# light_160mm_v1_0_less_vias.net
KiCad netlist of a schematic drawn in EAGLE
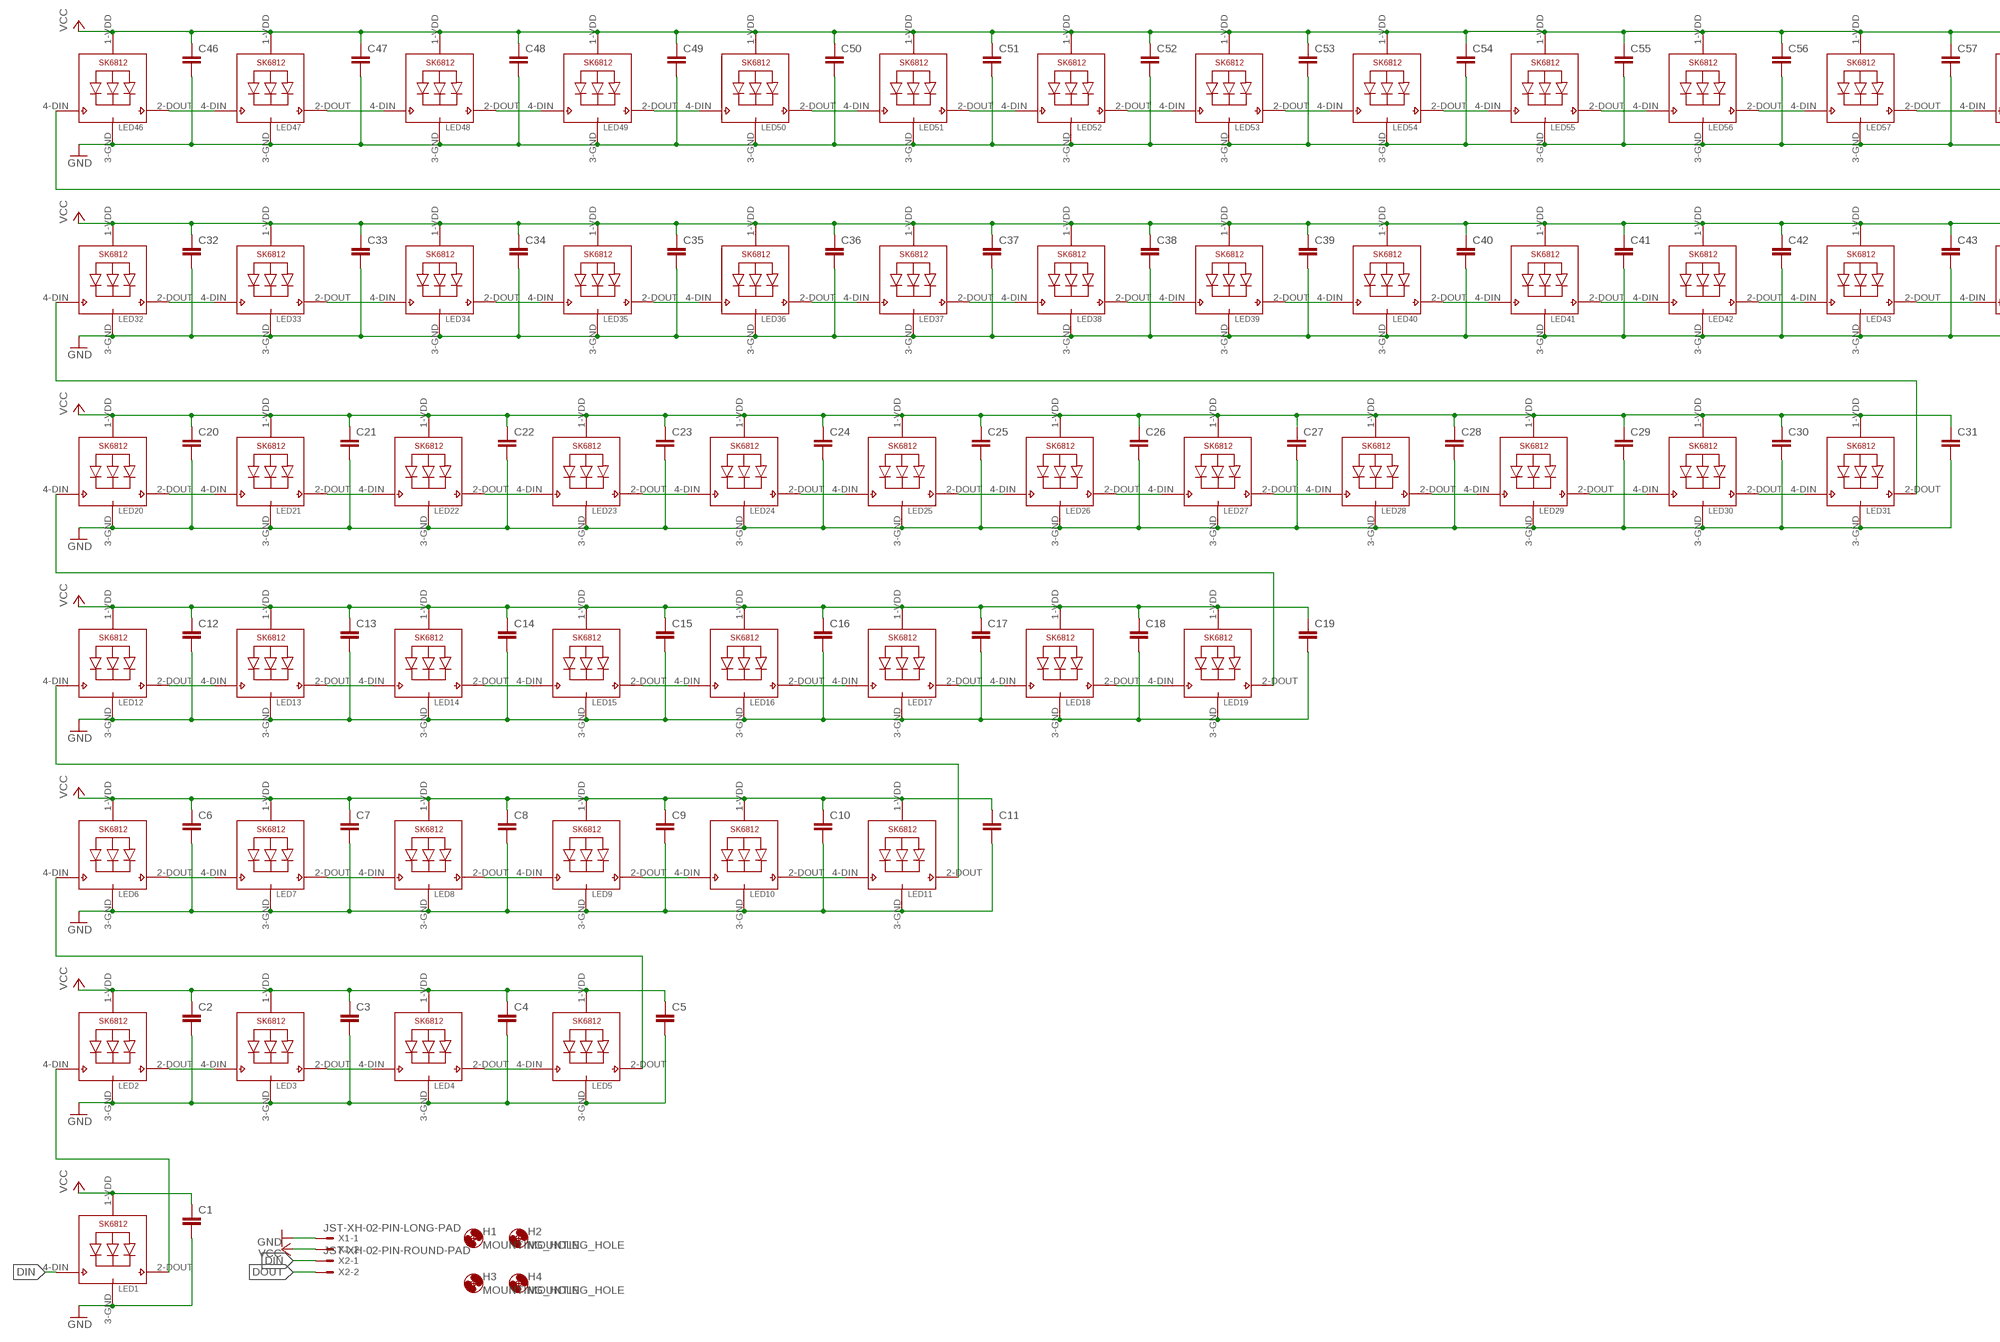
[diagram p0: schematic, sheet 1, part 1 of 2]
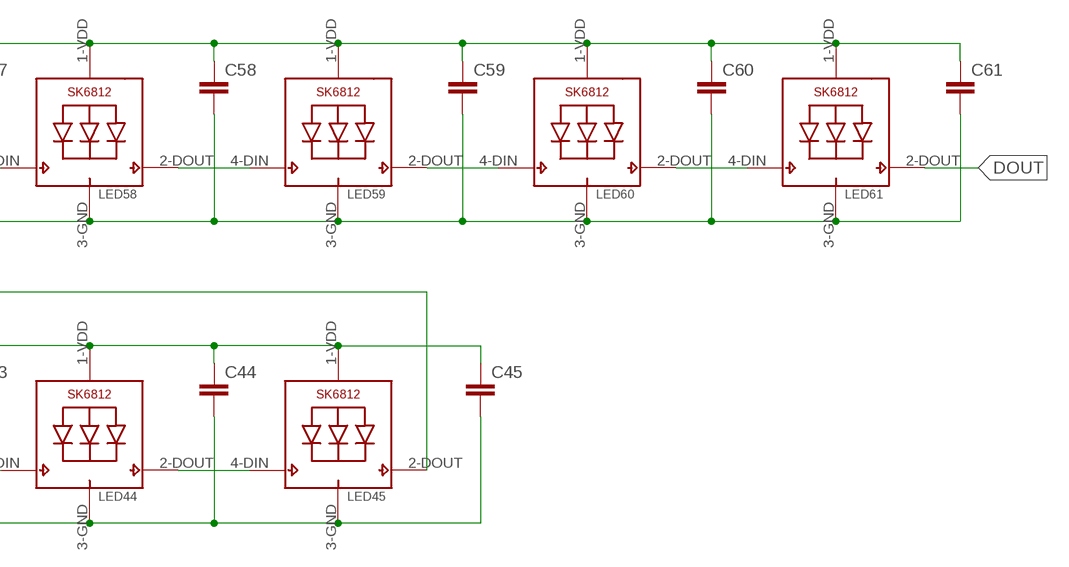
[diagram p1: schematic, sheet 1, part 2 of 2]

(export (version "E")
  (design (tool "Eeschema 10.0.6"))
  (components
    (comp (ref "C1")
      (value "C-EUC0805")
      (footprint "eagle-import:C0805")
      (libsource (lib "eagle-import") (part "C-EUC0805"))
    )
    (comp (ref "C2")
      (value "C-EUC0805")
      (footprint "eagle-import:C0805")
      (libsource (lib "eagle-import") (part "C-EUC0805"))
    )
    (comp (ref "C3")
      (value "C-EUC0805")
      (footprint "eagle-import:C0805")
      (libsource (lib "eagle-import") (part "C-EUC0805"))
    )
    (comp (ref "C4")
      (value "C-EUC0805")
      (footprint "eagle-import:C0805")
      (libsource (lib "eagle-import") (part "C-EUC0805"))
    )
    (comp (ref "C5")
      (value "C-EUC0805")
      (footprint "eagle-import:C0805")
      (libsource (lib "eagle-import") (part "C-EUC0805"))
    )
    (comp (ref "C6")
      (value "C-EUC0805")
      (footprint "eagle-import:C0805")
      (libsource (lib "eagle-import") (part "C-EUC0805"))
    )
    (comp (ref "C7")
      (value "C-EUC0805")
      (footprint "eagle-import:C0805")
      (libsource (lib "eagle-import") (part "C-EUC0805"))
    )
    (comp (ref "C8")
      (value "C-EUC0805")
      (footprint "eagle-import:C0805")
      (libsource (lib "eagle-import") (part "C-EUC0805"))
    )
    (comp (ref "C9")
      (value "C-EUC0805")
      (footprint "eagle-import:C0805")
      (libsource (lib "eagle-import") (part "C-EUC0805"))
    )
    (comp (ref "C10")
      (value "C-EUC0805")
      (footprint "eagle-import:C0805")
      (libsource (lib "eagle-import") (part "C-EUC0805"))
    )
    (comp (ref "C11")
      (value "C-EUC0805")
      (footprint "eagle-import:C0805")
      (libsource (lib "eagle-import") (part "C-EUC0805"))
    )
    (comp (ref "C12")
      (value "C-EUC0805")
      (footprint "eagle-import:C0805")
      (libsource (lib "eagle-import") (part "C-EUC0805"))
    )
    (comp (ref "C13")
      (value "C-EUC0805")
      (footprint "eagle-import:C0805")
      (libsource (lib "eagle-import") (part "C-EUC0805"))
    )
    (comp (ref "C14")
      (value "C-EUC0805")
      (footprint "eagle-import:C0805")
      (libsource (lib "eagle-import") (part "C-EUC0805"))
    )
    (comp (ref "C15")
      (value "C-EUC0805")
      (footprint "eagle-import:C0805")
      (libsource (lib "eagle-import") (part "C-EUC0805"))
    )
    (comp (ref "C16")
      (value "C-EUC0805")
      (footprint "eagle-import:C0805")
      (libsource (lib "eagle-import") (part "C-EUC0805"))
    )
    (comp (ref "C17")
      (value "C-EUC0805")
      (footprint "eagle-import:C0805")
      (libsource (lib "eagle-import") (part "C-EUC0805"))
    )
    (comp (ref "C18")
      (value "C-EUC0805")
      (footprint "eagle-import:C0805")
      (libsource (lib "eagle-import") (part "C-EUC0805"))
    )
    (comp (ref "C19")
      (value "C-EUC0805")
      (footprint "eagle-import:C0805")
      (libsource (lib "eagle-import") (part "C-EUC0805"))
    )
    (comp (ref "C20")
      (value "C-EUC0805")
      (footprint "eagle-import:C0805")
      (libsource (lib "eagle-import") (part "C-EUC0805"))
    )
    (comp (ref "C21")
      (value "C-EUC0805")
      (footprint "eagle-import:C0805")
      (libsource (lib "eagle-import") (part "C-EUC0805"))
    )
    (comp (ref "C22")
      (value "C-EUC0805")
      (footprint "eagle-import:C0805")
      (libsource (lib "eagle-import") (part "C-EUC0805"))
    )
    (comp (ref "C23")
      (value "C-EUC0805")
      (footprint "eagle-import:C0805")
      (libsource (lib "eagle-import") (part "C-EUC0805"))
    )
    (comp (ref "C24")
      (value "C-EUC0805")
      (footprint "eagle-import:C0805")
      (libsource (lib "eagle-import") (part "C-EUC0805"))
    )
    (comp (ref "C25")
      (value "C-EUC0805")
      (footprint "eagle-import:C0805")
      (libsource (lib "eagle-import") (part "C-EUC0805"))
    )
    (comp (ref "C26")
      (value "C-EUC0805")
      (footprint "eagle-import:C0805")
      (libsource (lib "eagle-import") (part "C-EUC0805"))
    )
    (comp (ref "C27")
      (value "C-EUC0805")
      (footprint "eagle-import:C0805")
      (libsource (lib "eagle-import") (part "C-EUC0805"))
    )
    (comp (ref "C28")
      (value "C-EUC0805")
      (footprint "eagle-import:C0805")
      (libsource (lib "eagle-import") (part "C-EUC0805"))
    )
    (comp (ref "C29")
      (value "C-EUC0805")
      (footprint "eagle-import:C0805")
      (libsource (lib "eagle-import") (part "C-EUC0805"))
    )
    (comp (ref "C30")
      (value "C-EUC0805")
      (footprint "eagle-import:C0805")
      (libsource (lib "eagle-import") (part "C-EUC0805"))
    )
    (comp (ref "C31")
      (value "C-EUC0805")
      (footprint "eagle-import:C0805")
      (libsource (lib "eagle-import") (part "C-EUC0805"))
    )
    (comp (ref "C32")
      (value "C-EUC0805")
      (footprint "eagle-import:C0805")
      (libsource (lib "eagle-import") (part "C-EUC0805"))
    )
    (comp (ref "C33")
      (value "C-EUC0805")
      (footprint "eagle-import:C0805")
      (libsource (lib "eagle-import") (part "C-EUC0805"))
    )
    (comp (ref "C34")
      (value "C-EUC0805")
      (footprint "eagle-import:C0805")
      (libsource (lib "eagle-import") (part "C-EUC0805"))
    )
    (comp (ref "C35")
      (value "C-EUC0805")
      (footprint "eagle-import:C0805")
      (libsource (lib "eagle-import") (part "C-EUC0805"))
    )
    (comp (ref "C36")
      (value "C-EUC0805")
      (footprint "eagle-import:C0805")
      (libsource (lib "eagle-import") (part "C-EUC0805"))
    )
    (comp (ref "C37")
      (value "C-EUC0805")
      (footprint "eagle-import:C0805")
      (libsource (lib "eagle-import") (part "C-EUC0805"))
    )
    (comp (ref "C38")
      (value "C-EUC0805")
      (footprint "eagle-import:C0805")
      (libsource (lib "eagle-import") (part "C-EUC0805"))
    )
    (comp (ref "C39")
      (value "C-EUC0805")
      (footprint "eagle-import:C0805")
      (libsource (lib "eagle-import") (part "C-EUC0805"))
    )
    (comp (ref "C40")
      (value "C-EUC0805")
      (footprint "eagle-import:C0805")
      (libsource (lib "eagle-import") (part "C-EUC0805"))
    )
    (comp (ref "C41")
      (value "C-EUC0805")
      (footprint "eagle-import:C0805")
      (libsource (lib "eagle-import") (part "C-EUC0805"))
    )
    (comp (ref "C42")
      (value "C-EUC0805")
      (footprint "eagle-import:C0805")
      (libsource (lib "eagle-import") (part "C-EUC0805"))
    )
    (comp (ref "C43")
      (value "C-EUC0805")
      (footprint "eagle-import:C0805")
      (libsource (lib "eagle-import") (part "C-EUC0805"))
    )
    (comp (ref "C44")
      (value "C-EUC0805")
      (footprint "eagle-import:C0805")
      (libsource (lib "eagle-import") (part "C-EUC0805"))
    )
    (comp (ref "C45")
      (value "C-EUC0805")
      (footprint "eagle-import:C0805")
      (libsource (lib "eagle-import") (part "C-EUC0805"))
    )
    (comp (ref "C46")
      (value "C-EUC0805")
      (footprint "eagle-import:C0805")
      (libsource (lib "eagle-import") (part "C-EUC0805"))
    )
    (comp (ref "C47")
      (value "C-EUC0805")
      (footprint "eagle-import:C0805")
      (libsource (lib "eagle-import") (part "C-EUC0805"))
    )
    (comp (ref "C48")
      (value "C-EUC0805")
      (footprint "eagle-import:C0805")
      (libsource (lib "eagle-import") (part "C-EUC0805"))
    )
    (comp (ref "C49")
      (value "C-EUC0805")
      (footprint "eagle-import:C0805")
      (libsource (lib "eagle-import") (part "C-EUC0805"))
    )
    (comp (ref "C50")
      (value "C-EUC0805")
      (footprint "eagle-import:C0805")
      (libsource (lib "eagle-import") (part "C-EUC0805"))
    )
    (comp (ref "C51")
      (value "C-EUC0805")
      (footprint "eagle-import:C0805")
      (libsource (lib "eagle-import") (part "C-EUC0805"))
    )
    (comp (ref "C52")
      (value "C-EUC0805")
      (footprint "eagle-import:C0805")
      (libsource (lib "eagle-import") (part "C-EUC0805"))
    )
    (comp (ref "C53")
      (value "C-EUC0805")
      (footprint "eagle-import:C0805")
      (libsource (lib "eagle-import") (part "C-EUC0805"))
    )
    (comp (ref "C54")
      (value "C-EUC0805")
      (footprint "eagle-import:C0805")
      (libsource (lib "eagle-import") (part "C-EUC0805"))
    )
    (comp (ref "C55")
      (value "C-EUC0805")
      (footprint "eagle-import:C0805")
      (libsource (lib "eagle-import") (part "C-EUC0805"))
    )
    (comp (ref "C56")
      (value "C-EUC0805")
      (footprint "eagle-import:C0805")
      (libsource (lib "eagle-import") (part "C-EUC0805"))
    )
    (comp (ref "C57")
      (value "C-EUC0805")
      (footprint "eagle-import:C0805")
      (libsource (lib "eagle-import") (part "C-EUC0805"))
    )
    (comp (ref "C58")
      (value "C-EUC0805")
      (footprint "eagle-import:C0805")
      (libsource (lib "eagle-import") (part "C-EUC0805"))
    )
    (comp (ref "C59")
      (value "C-EUC0805")
      (footprint "eagle-import:C0805")
      (libsource (lib "eagle-import") (part "C-EUC0805"))
    )
    (comp (ref "C60")
      (value "C-EUC0805")
      (footprint "eagle-import:C0805")
      (libsource (lib "eagle-import") (part "C-EUC0805"))
    )
    (comp (ref "C61")
      (value "C-EUC0805")
      (footprint "eagle-import:C0805")
      (libsource (lib "eagle-import") (part "C-EUC0805"))
    )
    (comp (ref "H1")
      (value "MOUNTING_HOLE")
      (footprint "eagle-import:4,1")
      (libsource (lib "eagle-import") (part "MOUNTING_HOLE"))
    )
    (comp (ref "H2")
      (value "MOUNTING_HOLE")
      (footprint "eagle-import:4,1")
      (libsource (lib "eagle-import") (part "MOUNTING_HOLE"))
    )
    (comp (ref "H3")
      (value "MOUNTING_HOLE")
      (footprint "eagle-import:4,1")
      (libsource (lib "eagle-import") (part "MOUNTING_HOLE"))
    )
    (comp (ref "H4")
      (value "MOUNTING_HOLE")
      (footprint "eagle-import:4,1")
      (libsource (lib "eagle-import") (part "MOUNTING_HOLE"))
    )
    (comp (ref "LED1")
      (value "SK6812_5050W")
      (footprint "eagle-import:LED5050_W")
      (libsource (lib "eagle-import") (part "SK6812_5050W"))
    )
    (comp (ref "LED2")
      (value "SK6812_5050W")
      (footprint "eagle-import:LED5050_W")
      (libsource (lib "eagle-import") (part "SK6812_5050W"))
    )
    (comp (ref "LED3")
      (value "SK6812_5050W")
      (footprint "eagle-import:LED5050_W")
      (libsource (lib "eagle-import") (part "SK6812_5050W"))
    )
    (comp (ref "LED4")
      (value "SK6812_5050W")
      (footprint "eagle-import:LED5050_W")
      (libsource (lib "eagle-import") (part "SK6812_5050W"))
    )
    (comp (ref "LED5")
      (value "SK6812_5050W")
      (footprint "eagle-import:LED5050_W")
      (libsource (lib "eagle-import") (part "SK6812_5050W"))
    )
    (comp (ref "LED6")
      (value "SK6812_5050W")
      (footprint "eagle-import:LED5050_W")
      (libsource (lib "eagle-import") (part "SK6812_5050W"))
    )
    (comp (ref "LED7")
      (value "SK6812_5050W")
      (footprint "eagle-import:LED5050_W")
      (libsource (lib "eagle-import") (part "SK6812_5050W"))
    )
    (comp (ref "LED8")
      (value "SK6812_5050W")
      (footprint "eagle-import:LED5050_W")
      (libsource (lib "eagle-import") (part "SK6812_5050W"))
    )
    (comp (ref "LED9")
      (value "SK6812_5050W")
      (footprint "eagle-import:LED5050_W")
      (libsource (lib "eagle-import") (part "SK6812_5050W"))
    )
    (comp (ref "LED10")
      (value "SK6812_5050W")
      (footprint "eagle-import:LED5050_W")
      (libsource (lib "eagle-import") (part "SK6812_5050W"))
    )
    (comp (ref "LED11")
      (value "SK6812_5050W")
      (footprint "eagle-import:LED5050_W")
      (libsource (lib "eagle-import") (part "SK6812_5050W"))
    )
    (comp (ref "LED12")
      (value "SK6812_5050W")
      (footprint "eagle-import:LED5050_W")
      (libsource (lib "eagle-import") (part "SK6812_5050W"))
    )
    (comp (ref "LED13")
      (value "SK6812_5050W")
      (footprint "eagle-import:LED5050_W")
      (libsource (lib "eagle-import") (part "SK6812_5050W"))
    )
    (comp (ref "LED14")
      (value "SK6812_5050W")
      (footprint "eagle-import:LED5050_W")
      (libsource (lib "eagle-import") (part "SK6812_5050W"))
    )
    (comp (ref "LED15")
      (value "SK6812_5050W")
      (footprint "eagle-import:LED5050_W")
      (libsource (lib "eagle-import") (part "SK6812_5050W"))
    )
    (comp (ref "LED16")
      (value "SK6812_5050W")
      (footprint "eagle-import:LED5050_W")
      (libsource (lib "eagle-import") (part "SK6812_5050W"))
    )
    (comp (ref "LED17")
      (value "SK6812_5050W")
      (footprint "eagle-import:LED5050_W")
      (libsource (lib "eagle-import") (part "SK6812_5050W"))
    )
    (comp (ref "LED18")
      (value "SK6812_5050W")
      (footprint "eagle-import:LED5050_W")
      (libsource (lib "eagle-import") (part "SK6812_5050W"))
    )
    (comp (ref "LED19")
      (value "SK6812_5050W")
      (footprint "eagle-import:LED5050_W")
      (libsource (lib "eagle-import") (part "SK6812_5050W"))
    )
    (comp (ref "LED20")
      (value "SK6812_5050W")
      (footprint "eagle-import:LED5050_W")
      (libsource (lib "eagle-import") (part "SK6812_5050W"))
    )
    (comp (ref "LED21")
      (value "SK6812_5050W")
      (footprint "eagle-import:LED5050_W")
      (libsource (lib "eagle-import") (part "SK6812_5050W"))
    )
    (comp (ref "LED22")
      (value "SK6812_5050W")
      (footprint "eagle-import:LED5050_W")
      (libsource (lib "eagle-import") (part "SK6812_5050W"))
    )
    (comp (ref "LED23")
      (value "SK6812_5050W")
      (footprint "eagle-import:LED5050_W")
      (libsource (lib "eagle-import") (part "SK6812_5050W"))
    )
    (comp (ref "LED24")
      (value "SK6812_5050W")
      (footprint "eagle-import:LED5050_W")
      (libsource (lib "eagle-import") (part "SK6812_5050W"))
    )
    (comp (ref "LED25")
      (value "SK6812_5050W")
      (footprint "eagle-import:LED5050_W")
      (libsource (lib "eagle-import") (part "SK6812_5050W"))
    )
    (comp (ref "LED26")
      (value "SK6812_5050W")
      (footprint "eagle-import:LED5050_W")
      (libsource (lib "eagle-import") (part "SK6812_5050W"))
    )
    (comp (ref "LED27")
      (value "SK6812_5050W")
      (footprint "eagle-import:LED5050_W")
      (libsource (lib "eagle-import") (part "SK6812_5050W"))
    )
    (comp (ref "LED28")
      (value "SK6812_5050W")
      (footprint "eagle-import:LED5050_W")
      (libsource (lib "eagle-import") (part "SK6812_5050W"))
    )
    (comp (ref "LED29")
      (value "SK6812_5050W")
      (footprint "eagle-import:LED5050_W")
      (libsource (lib "eagle-import") (part "SK6812_5050W"))
    )
    (comp (ref "LED30")
      (value "SK6812_5050W")
      (footprint "eagle-import:LED5050_W")
      (libsource (lib "eagle-import") (part "SK6812_5050W"))
    )
    (comp (ref "LED31")
      (value "SK6812_5050W")
      (footprint "eagle-import:LED5050_W")
      (libsource (lib "eagle-import") (part "SK6812_5050W"))
    )
    (comp (ref "LED32")
      (value "SK6812_5050W")
      (footprint "eagle-import:LED5050_W")
      (libsource (lib "eagle-import") (part "SK6812_5050W"))
    )
    (comp (ref "LED33")
      (value "SK6812_5050W")
      (footprint "eagle-import:LED5050_W")
      (libsource (lib "eagle-import") (part "SK6812_5050W"))
    )
    (comp (ref "LED34")
      (value "SK6812_5050W")
      (footprint "eagle-import:LED5050_W")
      (libsource (lib "eagle-import") (part "SK6812_5050W"))
    )
    (comp (ref "LED35")
      (value "SK6812_5050W")
      (footprint "eagle-import:LED5050_W")
      (libsource (lib "eagle-import") (part "SK6812_5050W"))
    )
    (comp (ref "LED36")
      (value "SK6812_5050W")
      (footprint "eagle-import:LED5050_W")
      (libsource (lib "eagle-import") (part "SK6812_5050W"))
    )
    (comp (ref "LED37")
      (value "SK6812_5050W")
      (footprint "eagle-import:LED5050_W")
      (libsource (lib "eagle-import") (part "SK6812_5050W"))
    )
    (comp (ref "LED38")
      (value "SK6812_5050W")
      (footprint "eagle-import:LED5050_W")
      (libsource (lib "eagle-import") (part "SK6812_5050W"))
    )
    (comp (ref "LED39")
      (value "SK6812_5050W")
      (footprint "eagle-import:LED5050_W")
      (libsource (lib "eagle-import") (part "SK6812_5050W"))
    )
    (comp (ref "LED40")
      (value "SK6812_5050W")
      (footprint "eagle-import:LED5050_W")
      (libsource (lib "eagle-import") (part "SK6812_5050W"))
    )
    (comp (ref "LED41")
      (value "SK6812_5050W")
      (footprint "eagle-import:LED5050_W")
      (libsource (lib "eagle-import") (part "SK6812_5050W"))
    )
    (comp (ref "LED42")
      (value "SK6812_5050W")
      (footprint "eagle-import:LED5050_W")
      (libsource (lib "eagle-import") (part "SK6812_5050W"))
    )
    (comp (ref "LED43")
      (value "SK6812_5050W")
      (footprint "eagle-import:LED5050_W")
      (libsource (lib "eagle-import") (part "SK6812_5050W"))
    )
    (comp (ref "LED44")
      (value "SK6812_5050W")
      (footprint "eagle-import:LED5050_W")
      (libsource (lib "eagle-import") (part "SK6812_5050W"))
    )
    (comp (ref "LED45")
      (value "SK6812_5050W")
      (footprint "eagle-import:LED5050_W")
      (libsource (lib "eagle-import") (part "SK6812_5050W"))
    )
    (comp (ref "LED46")
      (value "SK6812_5050W")
      (footprint "eagle-import:LED5050_W")
      (libsource (lib "eagle-import") (part "SK6812_5050W"))
    )
    (comp (ref "LED47")
      (value "SK6812_5050W")
      (footprint "eagle-import:LED5050_W")
      (libsource (lib "eagle-import") (part "SK6812_5050W"))
    )
    (comp (ref "LED48")
      (value "SK6812_5050W")
      (footprint "eagle-import:LED5050_W")
      (libsource (lib "eagle-import") (part "SK6812_5050W"))
    )
    (comp (ref "LED49")
      (value "SK6812_5050W")
      (footprint "eagle-import:LED5050_W")
      (libsource (lib "eagle-import") (part "SK6812_5050W"))
    )
    (comp (ref "LED50")
      (value "SK6812_5050W")
      (footprint "eagle-import:LED5050_W")
      (libsource (lib "eagle-import") (part "SK6812_5050W"))
    )
    (comp (ref "LED51")
      (value "SK6812_5050W")
      (footprint "eagle-import:LED5050_W")
      (libsource (lib "eagle-import") (part "SK6812_5050W"))
    )
    (comp (ref "LED52")
      (value "SK6812_5050W")
      (footprint "eagle-import:LED5050_W")
      (libsource (lib "eagle-import") (part "SK6812_5050W"))
    )
    (comp (ref "LED53")
      (value "SK6812_5050W")
      (footprint "eagle-import:LED5050_W")
      (libsource (lib "eagle-import") (part "SK6812_5050W"))
    )
    (comp (ref "LED54")
      (value "SK6812_5050W")
      (footprint "eagle-import:LED5050_W")
      (libsource (lib "eagle-import") (part "SK6812_5050W"))
    )
    (comp (ref "LED55")
      (value "SK6812_5050W")
      (footprint "eagle-import:LED5050_W")
      (libsource (lib "eagle-import") (part "SK6812_5050W"))
    )
    (comp (ref "LED56")
      (value "SK6812_5050W")
      (footprint "eagle-import:LED5050_W")
      (libsource (lib "eagle-import") (part "SK6812_5050W"))
    )
    (comp (ref "LED57")
      (value "SK6812_5050W")
      (footprint "eagle-import:LED5050_W")
      (libsource (lib "eagle-import") (part "SK6812_5050W"))
    )
    (comp (ref "LED58")
      (value "SK6812_5050W")
      (footprint "eagle-import:LED5050_W")
      (libsource (lib "eagle-import") (part "SK6812_5050W"))
    )
    (comp (ref "LED59")
      (value "SK6812_5050W")
      (footprint "eagle-import:LED5050_W")
      (libsource (lib "eagle-import") (part "SK6812_5050W"))
    )
    (comp (ref "LED60")
      (value "SK6812_5050W")
      (footprint "eagle-import:LED5050_W")
      (libsource (lib "eagle-import") (part "SK6812_5050W"))
    )
    (comp (ref "LED61")
      (value "SK6812_5050W")
      (footprint "eagle-import:LED5050_W")
      (libsource (lib "eagle-import") (part "SK6812_5050W"))
    )
    (comp (ref "X1")
      (value "JST-XH-02-PIN-LONG-PAD")
      (footprint "eagle-import:JST-XH-02-PACKAGE-LONG-PAD")
      (libsource (lib "eagle-import") (part "JST-XH-02-PIN-LONG-PAD"))
    )
    (comp (ref "X2")
      (value "JST-XH-02-PIN-ROUND-PAD")
      (footprint "eagle-import:JST-XH-02-PACKAGE-ROUND-PAD")
      (libsource (lib "eagle-import") (part "JST-XH-02-PIN-ROUND-PAD"))
    )
  )
  (nets
    (net (code "1") (name "DIN") (class "Default")
      (node (ref "LED1") (pin "4-DIN") (pinfunction "DI_4-DIN") (pintype "input"))
      (node (ref "X2") (pin "1") (pinfunction "S_1") (pintype "passive"))
    )
    (net (code "2") (name "DOUT") (class "Default")
      (node (ref "LED61") (pin "2-DOUT") (pinfunction "DO_2-DOUT") (pintype "output"))
      (node (ref "X2") (pin "2") (pinfunction "S_2") (pintype "passive"))
    )
    (net (code "3") (name "GND") (class "Default")
      (node (ref "C1") (pin "2") (pinfunction "2_2") (pintype "passive"))
      (node (ref "C10") (pin "2") (pinfunction "2_2") (pintype "passive"))
      (node (ref "C11") (pin "2") (pinfunction "2_2") (pintype "passive"))
      (node (ref "C12") (pin "2") (pinfunction "2_2") (pintype "passive"))
      (node (ref "C13") (pin "2") (pinfunction "2_2") (pintype "passive"))
      (node (ref "C14") (pin "2") (pinfunction "2_2") (pintype "passive"))
      (node (ref "C15") (pin "2") (pinfunction "2_2") (pintype "passive"))
      (node (ref "C16") (pin "2") (pinfunction "2_2") (pintype "passive"))
      (node (ref "C17") (pin "2") (pinfunction "2_2") (pintype "passive"))
      (node (ref "C18") (pin "2") (pinfunction "2_2") (pintype "passive"))
      (node (ref "C19") (pin "2") (pinfunction "2_2") (pintype "passive"))
      (node (ref "C2") (pin "2") (pinfunction "2_2") (pintype "passive"))
      (node (ref "C20") (pin "2") (pinfunction "2_2") (pintype "passive"))
      (node (ref "C21") (pin "2") (pinfunction "2_2") (pintype "passive"))
      (node (ref "C22") (pin "2") (pinfunction "2_2") (pintype "passive"))
      (node (ref "C23") (pin "2") (pinfunction "2_2") (pintype "passive"))
      (node (ref "C24") (pin "2") (pinfunction "2_2") (pintype "passive"))
      (node (ref "C25") (pin "2") (pinfunction "2_2") (pintype "passive"))
      (node (ref "C26") (pin "2") (pinfunction "2_2") (pintype "passive"))
      (node (ref "C27") (pin "2") (pinfunction "2_2") (pintype "passive"))
      (node (ref "C28") (pin "2") (pinfunction "2_2") (pintype "passive"))
      (node (ref "C29") (pin "2") (pinfunction "2_2") (pintype "passive"))
      (node (ref "C3") (pin "2") (pinfunction "2_2") (pintype "passive"))
      (node (ref "C30") (pin "2") (pinfunction "2_2") (pintype "passive"))
      (node (ref "C31") (pin "2") (pinfunction "2_2") (pintype "passive"))
      (node (ref "C32") (pin "2") (pinfunction "2_2") (pintype "passive"))
      (node (ref "C33") (pin "2") (pinfunction "2_2") (pintype "passive"))
      (node (ref "C34") (pin "2") (pinfunction "2_2") (pintype "passive"))
      (node (ref "C35") (pin "2") (pinfunction "2_2") (pintype "passive"))
      (node (ref "C36") (pin "2") (pinfunction "2_2") (pintype "passive"))
      (node (ref "C37") (pin "2") (pinfunction "2_2") (pintype "passive"))
      (node (ref "C38") (pin "2") (pinfunction "2_2") (pintype "passive"))
      (node (ref "C39") (pin "2") (pinfunction "2_2") (pintype "passive"))
      (node (ref "C4") (pin "2") (pinfunction "2_2") (pintype "passive"))
      (node (ref "C40") (pin "2") (pinfunction "2_2") (pintype "passive"))
      (node (ref "C41") (pin "2") (pinfunction "2_2") (pintype "passive"))
      (node (ref "C42") (pin "2") (pinfunction "2_2") (pintype "passive"))
      (node (ref "C43") (pin "2") (pinfunction "2_2") (pintype "passive"))
      (node (ref "C44") (pin "2") (pinfunction "2_2") (pintype "passive"))
      (node (ref "C45") (pin "2") (pinfunction "2_2") (pintype "passive"))
      (node (ref "C46") (pin "2") (pinfunction "2_2") (pintype "passive"))
      (node (ref "C47") (pin "2") (pinfunction "2_2") (pintype "passive"))
      (node (ref "C48") (pin "2") (pinfunction "2_2") (pintype "passive"))
      (node (ref "C49") (pin "2") (pinfunction "2_2") (pintype "passive"))
      (node (ref "C5") (pin "2") (pinfunction "2_2") (pintype "passive"))
      (node (ref "C50") (pin "2") (pinfunction "2_2") (pintype "passive"))
      (node (ref "C51") (pin "2") (pinfunction "2_2") (pintype "passive"))
      (node (ref "C52") (pin "2") (pinfunction "2_2") (pintype "passive"))
      (node (ref "C53") (pin "2") (pinfunction "2_2") (pintype "passive"))
      (node (ref "C54") (pin "2") (pinfunction "2_2") (pintype "passive"))
      (node (ref "C55") (pin "2") (pinfunction "2_2") (pintype "passive"))
      (node (ref "C56") (pin "2") (pinfunction "2_2") (pintype "passive"))
      (node (ref "C57") (pin "2") (pinfunction "2_2") (pintype "passive"))
      (node (ref "C58") (pin "2") (pinfunction "2_2") (pintype "passive"))
      (node (ref "C59") (pin "2") (pinfunction "2_2") (pintype "passive"))
      (node (ref "C6") (pin "2") (pinfunction "2_2") (pintype "passive"))
      (node (ref "C60") (pin "2") (pinfunction "2_2") (pintype "passive"))
      (node (ref "C61") (pin "2") (pinfunction "2_2") (pintype "passive"))
      (node (ref "C7") (pin "2") (pinfunction "2_2") (pintype "passive"))
      (node (ref "C8") (pin "2") (pinfunction "2_2") (pintype "passive"))
      (node (ref "C9") (pin "2") (pinfunction "2_2") (pintype "passive"))
      (node (ref "LED1") (pin "3-GND") (pinfunction "GND_3-GND") (pintype "power_in"))
      (node (ref "LED10") (pin "3-GND") (pinfunction "GND_3-GND") (pintype "power_in"))
      (node (ref "LED11") (pin "3-GND") (pinfunction "GND_3-GND") (pintype "power_in"))
      (node (ref "LED12") (pin "3-GND") (pinfunction "GND_3-GND") (pintype "power_in"))
      (node (ref "LED13") (pin "3-GND") (pinfunction "GND_3-GND") (pintype "power_in"))
      (node (ref "LED14") (pin "3-GND") (pinfunction "GND_3-GND") (pintype "power_in"))
      (node (ref "LED15") (pin "3-GND") (pinfunction "GND_3-GND") (pintype "power_in"))
      (node (ref "LED16") (pin "3-GND") (pinfunction "GND_3-GND") (pintype "power_in"))
      (node (ref "LED17") (pin "3-GND") (pinfunction "GND_3-GND") (pintype "power_in"))
      (node (ref "LED18") (pin "3-GND") (pinfunction "GND_3-GND") (pintype "power_in"))
      (node (ref "LED19") (pin "3-GND") (pinfunction "GND_3-GND") (pintype "power_in"))
      (node (ref "LED2") (pin "3-GND") (pinfunction "GND_3-GND") (pintype "power_in"))
      (node (ref "LED20") (pin "3-GND") (pinfunction "GND_3-GND") (pintype "power_in"))
      (node (ref "LED21") (pin "3-GND") (pinfunction "GND_3-GND") (pintype "power_in"))
      (node (ref "LED22") (pin "3-GND") (pinfunction "GND_3-GND") (pintype "power_in"))
      (node (ref "LED23") (pin "3-GND") (pinfunction "GND_3-GND") (pintype "power_in"))
      (node (ref "LED24") (pin "3-GND") (pinfunction "GND_3-GND") (pintype "power_in"))
      (node (ref "LED25") (pin "3-GND") (pinfunction "GND_3-GND") (pintype "power_in"))
      (node (ref "LED26") (pin "3-GND") (pinfunction "GND_3-GND") (pintype "power_in"))
      (node (ref "LED27") (pin "3-GND") (pinfunction "GND_3-GND") (pintype "power_in"))
      (node (ref "LED28") (pin "3-GND") (pinfunction "GND_3-GND") (pintype "power_in"))
      (node (ref "LED29") (pin "3-GND") (pinfunction "GND_3-GND") (pintype "power_in"))
      (node (ref "LED3") (pin "3-GND") (pinfunction "GND_3-GND") (pintype "power_in"))
      (node (ref "LED30") (pin "3-GND") (pinfunction "GND_3-GND") (pintype "power_in"))
      (node (ref "LED31") (pin "3-GND") (pinfunction "GND_3-GND") (pintype "power_in"))
      (node (ref "LED32") (pin "3-GND") (pinfunction "GND_3-GND") (pintype "power_in"))
      (node (ref "LED33") (pin "3-GND") (pinfunction "GND_3-GND") (pintype "power_in"))
      (node (ref "LED34") (pin "3-GND") (pinfunction "GND_3-GND") (pintype "power_in"))
      (node (ref "LED35") (pin "3-GND") (pinfunction "GND_3-GND") (pintype "power_in"))
      (node (ref "LED36") (pin "3-GND") (pinfunction "GND_3-GND") (pintype "power_in"))
      (node (ref "LED37") (pin "3-GND") (pinfunction "GND_3-GND") (pintype "power_in"))
      (node (ref "LED38") (pin "3-GND") (pinfunction "GND_3-GND") (pintype "power_in"))
      (node (ref "LED39") (pin "3-GND") (pinfunction "GND_3-GND") (pintype "power_in"))
      (node (ref "LED4") (pin "3-GND") (pinfunction "GND_3-GND") (pintype "power_in"))
      (node (ref "LED40") (pin "3-GND") (pinfunction "GND_3-GND") (pintype "power_in"))
      (node (ref "LED41") (pin "3-GND") (pinfunction "GND_3-GND") (pintype "power_in"))
      (node (ref "LED42") (pin "3-GND") (pinfunction "GND_3-GND") (pintype "power_in"))
      (node (ref "LED43") (pin "3-GND") (pinfunction "GND_3-GND") (pintype "power_in"))
      (node (ref "LED44") (pin "3-GND") (pinfunction "GND_3-GND") (pintype "power_in"))
      (node (ref "LED45") (pin "3-GND") (pinfunction "GND_3-GND") (pintype "power_in"))
      (node (ref "LED46") (pin "3-GND") (pinfunction "GND_3-GND") (pintype "power_in"))
      (node (ref "LED47") (pin "3-GND") (pinfunction "GND_3-GND") (pintype "power_in"))
      (node (ref "LED48") (pin "3-GND") (pinfunction "GND_3-GND") (pintype "power_in"))
      (node (ref "LED49") (pin "3-GND") (pinfunction "GND_3-GND") (pintype "power_in"))
      (node (ref "LED5") (pin "3-GND") (pinfunction "GND_3-GND") (pintype "power_in"))
      (node (ref "LED50") (pin "3-GND") (pinfunction "GND_3-GND") (pintype "power_in"))
      (node (ref "LED51") (pin "3-GND") (pinfunction "GND_3-GND") (pintype "power_in"))
      (node (ref "LED52") (pin "3-GND") (pinfunction "GND_3-GND") (pintype "power_in"))
      (node (ref "LED53") (pin "3-GND") (pinfunction "GND_3-GND") (pintype "power_in"))
      (node (ref "LED54") (pin "3-GND") (pinfunction "GND_3-GND") (pintype "power_in"))
      (node (ref "LED55") (pin "3-GND") (pinfunction "GND_3-GND") (pintype "power_in"))
      (node (ref "LED56") (pin "3-GND") (pinfunction "GND_3-GND") (pintype "power_in"))
      (node (ref "LED57") (pin "3-GND") (pinfunction "GND_3-GND") (pintype "power_in"))
      (node (ref "LED58") (pin "3-GND") (pinfunction "GND_3-GND") (pintype "power_in"))
      (node (ref "LED59") (pin "3-GND") (pinfunction "GND_3-GND") (pintype "power_in"))
      (node (ref "LED6") (pin "3-GND") (pinfunction "GND_3-GND") (pintype "power_in"))
      (node (ref "LED60") (pin "3-GND") (pinfunction "GND_3-GND") (pintype "power_in"))
      (node (ref "LED61") (pin "3-GND") (pinfunction "GND_3-GND") (pintype "power_in"))
      (node (ref "LED7") (pin "3-GND") (pinfunction "GND_3-GND") (pintype "power_in"))
      (node (ref "LED8") (pin "3-GND") (pinfunction "GND_3-GND") (pintype "power_in"))
      (node (ref "LED9") (pin "3-GND") (pinfunction "GND_3-GND") (pintype "power_in"))
      (node (ref "X1") (pin "1") (pinfunction "S_1") (pintype "passive"))
    )
    (net (code "4") (name "Net-(LED1-DO)") (class "Default")
      (node (ref "LED1") (pin "2-DOUT") (pinfunction "DO_2-DOUT") (pintype "output"))
      (node (ref "LED2") (pin "4-DIN") (pinfunction "DI_4-DIN") (pintype "input"))
    )
    (net (code "5") (name "Net-(LED2-DO)") (class "Default")
      (node (ref "LED2") (pin "2-DOUT") (pinfunction "DO_2-DOUT") (pintype "output"))
      (node (ref "LED3") (pin "4-DIN") (pinfunction "DI_4-DIN") (pintype "input"))
    )
    (net (code "6") (name "Net-(LED3-DO)") (class "Default")
      (node (ref "LED3") (pin "2-DOUT") (pinfunction "DO_2-DOUT") (pintype "output"))
      (node (ref "LED4") (pin "4-DIN") (pinfunction "DI_4-DIN") (pintype "input"))
    )
    (net (code "7") (name "Net-(LED4-DO)") (class "Default")
      (node (ref "LED4") (pin "2-DOUT") (pinfunction "DO_2-DOUT") (pintype "output"))
      (node (ref "LED5") (pin "4-DIN") (pinfunction "DI_4-DIN") (pintype "input"))
    )
    (net (code "8") (name "Net-(LED5-DO)") (class "Default")
      (node (ref "LED5") (pin "2-DOUT") (pinfunction "DO_2-DOUT") (pintype "output"))
      (node (ref "LED6") (pin "4-DIN") (pinfunction "DI_4-DIN") (pintype "input"))
    )
    (net (code "9") (name "Net-(LED6-DO)") (class "Default")
      (node (ref "LED6") (pin "2-DOUT") (pinfunction "DO_2-DOUT") (pintype "output"))
      (node (ref "LED7") (pin "4-DIN") (pinfunction "DI_4-DIN") (pintype "input"))
    )
    (net (code "10") (name "Net-(LED7-DO)") (class "Default")
      (node (ref "LED7") (pin "2-DOUT") (pinfunction "DO_2-DOUT") (pintype "output"))
      (node (ref "LED8") (pin "4-DIN") (pinfunction "DI_4-DIN") (pintype "input"))
    )
    (net (code "11") (name "Net-(LED8-DO)") (class "Default")
      (node (ref "LED8") (pin "2-DOUT") (pinfunction "DO_2-DOUT") (pintype "output"))
      (node (ref "LED9") (pin "4-DIN") (pinfunction "DI_4-DIN") (pintype "input"))
    )
    (net (code "12") (name "Net-(LED10-DI)") (class "Default")
      (node (ref "LED10") (pin "4-DIN") (pinfunction "DI_4-DIN") (pintype "input"))
      (node (ref "LED9") (pin "2-DOUT") (pinfunction "DO_2-DOUT") (pintype "output"))
    )
    (net (code "13") (name "Net-(LED10-DO)") (class "Default")
      (node (ref "LED10") (pin "2-DOUT") (pinfunction "DO_2-DOUT") (pintype "output"))
      (node (ref "LED11") (pin "4-DIN") (pinfunction "DI_4-DIN") (pintype "input"))
    )
    (net (code "14") (name "Net-(LED11-DO)") (class "Default")
      (node (ref "LED11") (pin "2-DOUT") (pinfunction "DO_2-DOUT") (pintype "output"))
      (node (ref "LED12") (pin "4-DIN") (pinfunction "DI_4-DIN") (pintype "input"))
    )
    (net (code "15") (name "Net-(LED12-DO)") (class "Default")
      (node (ref "LED12") (pin "2-DOUT") (pinfunction "DO_2-DOUT") (pintype "output"))
      (node (ref "LED13") (pin "4-DIN") (pinfunction "DI_4-DIN") (pintype "input"))
    )
    (net (code "16") (name "Net-(LED13-DO)") (class "Default")
      (node (ref "LED13") (pin "2-DOUT") (pinfunction "DO_2-DOUT") (pintype "output"))
      (node (ref "LED14") (pin "4-DIN") (pinfunction "DI_4-DIN") (pintype "input"))
    )
    (net (code "17") (name "Net-(LED14-DO)") (class "Default")
      (node (ref "LED14") (pin "2-DOUT") (pinfunction "DO_2-DOUT") (pintype "output"))
      (node (ref "LED15") (pin "4-DIN") (pinfunction "DI_4-DIN") (pintype "input"))
    )
    (net (code "18") (name "Net-(LED15-DO)") (class "Default")
      (node (ref "LED15") (pin "2-DOUT") (pinfunction "DO_2-DOUT") (pintype "output"))
      (node (ref "LED16") (pin "4-DIN") (pinfunction "DI_4-DIN") (pintype "input"))
    )
    (net (code "19") (name "Net-(LED16-DO)") (class "Default")
      (node (ref "LED16") (pin "2-DOUT") (pinfunction "DO_2-DOUT") (pintype "output"))
      (node (ref "LED17") (pin "4-DIN") (pinfunction "DI_4-DIN") (pintype "input"))
    )
    (net (code "20") (name "Net-(LED17-DO)") (class "Default")
      (node (ref "LED17") (pin "2-DOUT") (pinfunction "DO_2-DOUT") (pintype "output"))
      (node (ref "LED18") (pin "4-DIN") (pinfunction "DI_4-DIN") (pintype "input"))
    )
    (net (code "21") (name "Net-(LED18-DO)") (class "Default")
      (node (ref "LED18") (pin "2-DOUT") (pinfunction "DO_2-DOUT") (pintype "output"))
      (node (ref "LED19") (pin "4-DIN") (pinfunction "DI_4-DIN") (pintype "input"))
    )
    (net (code "22") (name "Net-(LED19-DO)") (class "Default")
      (node (ref "LED19") (pin "2-DOUT") (pinfunction "DO_2-DOUT") (pintype "output"))
      (node (ref "LED20") (pin "4-DIN") (pinfunction "DI_4-DIN") (pintype "input"))
    )
    (net (code "23") (name "Net-(LED20-DO)") (class "Default")
      (node (ref "LED20") (pin "2-DOUT") (pinfunction "DO_2-DOUT") (pintype "output"))
      (node (ref "LED21") (pin "4-DIN") (pinfunction "DI_4-DIN") (pintype "input"))
    )
    (net (code "24") (name "Net-(LED21-DO)") (class "Default")
      (node (ref "LED21") (pin "2-DOUT") (pinfunction "DO_2-DOUT") (pintype "output"))
      (node (ref "LED22") (pin "4-DIN") (pinfunction "DI_4-DIN") (pintype "input"))
    )
    (net (code "25") (name "Net-(LED22-DO)") (class "Default")
      (node (ref "LED22") (pin "2-DOUT") (pinfunction "DO_2-DOUT") (pintype "output"))
      (node (ref "LED23") (pin "4-DIN") (pinfunction "DI_4-DIN") (pintype "input"))
    )
    (net (code "26") (name "Net-(LED23-DO)") (class "Default")
      (node (ref "LED23") (pin "2-DOUT") (pinfunction "DO_2-DOUT") (pintype "output"))
      (node (ref "LED24") (pin "4-DIN") (pinfunction "DI_4-DIN") (pintype "input"))
    )
    (net (code "27") (name "Net-(LED24-DO)") (class "Default")
      (node (ref "LED24") (pin "2-DOUT") (pinfunction "DO_2-DOUT") (pintype "output"))
      (node (ref "LED25") (pin "4-DIN") (pinfunction "DI_4-DIN") (pintype "input"))
    )
    (net (code "28") (name "Net-(LED25-DO)") (class "Default")
      (node (ref "LED25") (pin "2-DOUT") (pinfunction "DO_2-DOUT") (pintype "output"))
      (node (ref "LED26") (pin "4-DIN") (pinfunction "DI_4-DIN") (pintype "input"))
    )
    (net (code "29") (name "Net-(LED26-DO)") (class "Default")
      (node (ref "LED26") (pin "2-DOUT") (pinfunction "DO_2-DOUT") (pintype "output"))
      (node (ref "LED27") (pin "4-DIN") (pinfunction "DI_4-DIN") (pintype "input"))
    )
    (net (code "30") (name "Net-(LED27-DO)") (class "Default")
      (node (ref "LED27") (pin "2-DOUT") (pinfunction "DO_2-DOUT") (pintype "output"))
      (node (ref "LED28") (pin "4-DIN") (pinfunction "DI_4-DIN") (pintype "input"))
    )
    (net (code "31") (name "Net-(LED28-DO)") (class "Default")
      (node (ref "LED28") (pin "2-DOUT") (pinfunction "DO_2-DOUT") (pintype "output"))
      (node (ref "LED29") (pin "4-DIN") (pinfunction "DI_4-DIN") (pintype "input"))
    )
    (net (code "32") (name "Net-(LED29-DO)") (class "Default")
      (node (ref "LED29") (pin "2-DOUT") (pinfunction "DO_2-DOUT") (pintype "output"))
      (node (ref "LED30") (pin "4-DIN") (pinfunction "DI_4-DIN") (pintype "input"))
    )
    (net (code "33") (name "Net-(LED30-DO)") (class "Default")
      (node (ref "LED30") (pin "2-DOUT") (pinfunction "DO_2-DOUT") (pintype "output"))
      (node (ref "LED31") (pin "4-DIN") (pinfunction "DI_4-DIN") (pintype "input"))
    )
    (net (code "34") (name "Net-(LED31-DO)") (class "Default")
      (node (ref "LED31") (pin "2-DOUT") (pinfunction "DO_2-DOUT") (pintype "output"))
      (node (ref "LED32") (pin "4-DIN") (pinfunction "DI_4-DIN") (pintype "input"))
    )
    (net (code "35") (name "Net-(LED32-DO)") (class "Default")
      (node (ref "LED32") (pin "2-DOUT") (pinfunction "DO_2-DOUT") (pintype "output"))
      (node (ref "LED33") (pin "4-DIN") (pinfunction "DI_4-DIN") (pintype "input"))
    )
    (net (code "36") (name "Net-(LED33-DO)") (class "Default")
      (node (ref "LED33") (pin "2-DOUT") (pinfunction "DO_2-DOUT") (pintype "output"))
      (node (ref "LED34") (pin "4-DIN") (pinfunction "DI_4-DIN") (pintype "input"))
    )
    (net (code "37") (name "Net-(LED34-DO)") (class "Default")
      (node (ref "LED34") (pin "2-DOUT") (pinfunction "DO_2-DOUT") (pintype "output"))
      (node (ref "LED35") (pin "4-DIN") (pinfunction "DI_4-DIN") (pintype "input"))
    )
    (net (code "38") (name "Net-(LED35-DO)") (class "Default")
      (node (ref "LED35") (pin "2-DOUT") (pinfunction "DO_2-DOUT") (pintype "output"))
      (node (ref "LED36") (pin "4-DIN") (pinfunction "DI_4-DIN") (pintype "input"))
    )
    (net (code "39") (name "Net-(LED36-DO)") (class "Default")
      (node (ref "LED36") (pin "2-DOUT") (pinfunction "DO_2-DOUT") (pintype "output"))
      (node (ref "LED37") (pin "4-DIN") (pinfunction "DI_4-DIN") (pintype "input"))
    )
    (net (code "40") (name "Net-(LED37-DO)") (class "Default")
      (node (ref "LED37") (pin "2-DOUT") (pinfunction "DO_2-DOUT") (pintype "output"))
      (node (ref "LED38") (pin "4-DIN") (pinfunction "DI_4-DIN") (pintype "input"))
    )
    (net (code "41") (name "Net-(LED38-DO)") (class "Default")
      (node (ref "LED38") (pin "2-DOUT") (pinfunction "DO_2-DOUT") (pintype "output"))
      (node (ref "LED39") (pin "4-DIN") (pinfunction "DI_4-DIN") (pintype "input"))
    )
    (net (code "42") (name "Net-(LED39-DO)") (class "Default")
      (node (ref "LED39") (pin "2-DOUT") (pinfunction "DO_2-DOUT") (pintype "output"))
      (node (ref "LED40") (pin "4-DIN") (pinfunction "DI_4-DIN") (pintype "input"))
    )
    (net (code "43") (name "Net-(LED40-DO)") (class "Default")
      (node (ref "LED40") (pin "2-DOUT") (pinfunction "DO_2-DOUT") (pintype "output"))
      (node (ref "LED41") (pin "4-DIN") (pinfunction "DI_4-DIN") (pintype "input"))
    )
    (net (code "44") (name "Net-(LED41-DO)") (class "Default")
      (node (ref "LED41") (pin "2-DOUT") (pinfunction "DO_2-DOUT") (pintype "output"))
      (node (ref "LED42") (pin "4-DIN") (pinfunction "DI_4-DIN") (pintype "input"))
    )
    (net (code "45") (name "Net-(LED42-DO)") (class "Default")
      (node (ref "LED42") (pin "2-DOUT") (pinfunction "DO_2-DOUT") (pintype "output"))
      (node (ref "LED43") (pin "4-DIN") (pinfunction "DI_4-DIN") (pintype "input"))
    )
    (net (code "46") (name "Net-(LED43-DO)") (class "Default")
      (node (ref "LED43") (pin "2-DOUT") (pinfunction "DO_2-DOUT") (pintype "output"))
      (node (ref "LED44") (pin "4-DIN") (pinfunction "DI_4-DIN") (pintype "input"))
    )
    (net (code "47") (name "Net-(LED44-DO)") (class "Default")
      (node (ref "LED44") (pin "2-DOUT") (pinfunction "DO_2-DOUT") (pintype "output"))
      (node (ref "LED45") (pin "4-DIN") (pinfunction "DI_4-DIN") (pintype "input"))
    )
    (net (code "48") (name "Net-(LED45-DO)") (class "Default")
      (node (ref "LED45") (pin "2-DOUT") (pinfunction "DO_2-DOUT") (pintype "output"))
      (node (ref "LED46") (pin "4-DIN") (pinfunction "DI_4-DIN") (pintype "input"))
    )
    (net (code "49") (name "Net-(LED46-DO)") (class "Default")
      (node (ref "LED46") (pin "2-DOUT") (pinfunction "DO_2-DOUT") (pintype "output"))
      (node (ref "LED47") (pin "4-DIN") (pinfunction "DI_4-DIN") (pintype "input"))
    )
    (net (code "50") (name "Net-(LED47-DO)") (class "Default")
      (node (ref "LED47") (pin "2-DOUT") (pinfunction "DO_2-DOUT") (pintype "output"))
      (node (ref "LED48") (pin "4-DIN") (pinfunction "DI_4-DIN") (pintype "input"))
    )
    (net (code "51") (name "Net-(LED48-DO)") (class "Default")
      (node (ref "LED48") (pin "2-DOUT") (pinfunction "DO_2-DOUT") (pintype "output"))
      (node (ref "LED49") (pin "4-DIN") (pinfunction "DI_4-DIN") (pintype "input"))
    )
    (net (code "52") (name "Net-(LED49-DO)") (class "Default")
      (node (ref "LED49") (pin "2-DOUT") (pinfunction "DO_2-DOUT") (pintype "output"))
      (node (ref "LED50") (pin "4-DIN") (pinfunction "DI_4-DIN") (pintype "input"))
    )
    (net (code "53") (name "Net-(LED50-DO)") (class "Default")
      (node (ref "LED50") (pin "2-DOUT") (pinfunction "DO_2-DOUT") (pintype "output"))
      (node (ref "LED51") (pin "4-DIN") (pinfunction "DI_4-DIN") (pintype "input"))
    )
    (net (code "54") (name "Net-(LED51-DO)") (class "Default")
      (node (ref "LED51") (pin "2-DOUT") (pinfunction "DO_2-DOUT") (pintype "output"))
      (node (ref "LED52") (pin "4-DIN") (pinfunction "DI_4-DIN") (pintype "input"))
    )
    (net (code "55") (name "Net-(LED52-DO)") (class "Default")
      (node (ref "LED52") (pin "2-DOUT") (pinfunction "DO_2-DOUT") (pintype "output"))
      (node (ref "LED53") (pin "4-DIN") (pinfunction "DI_4-DIN") (pintype "input"))
    )
    (net (code "56") (name "Net-(LED53-DO)") (class "Default")
      (node (ref "LED53") (pin "2-DOUT") (pinfunction "DO_2-DOUT") (pintype "output"))
      (node (ref "LED54") (pin "4-DIN") (pinfunction "DI_4-DIN") (pintype "input"))
    )
    (net (code "57") (name "Net-(LED54-DO)") (class "Default")
      (node (ref "LED54") (pin "2-DOUT") (pinfunction "DO_2-DOUT") (pintype "output"))
      (node (ref "LED55") (pin "4-DIN") (pinfunction "DI_4-DIN") (pintype "input"))
    )
    (net (code "58") (name "Net-(LED55-DO)") (class "Default")
      (node (ref "LED55") (pin "2-DOUT") (pinfunction "DO_2-DOUT") (pintype "output"))
      (node (ref "LED56") (pin "4-DIN") (pinfunction "DI_4-DIN") (pintype "input"))
    )
    (net (code "59") (name "Net-(LED56-DO)") (class "Default")
      (node (ref "LED56") (pin "2-DOUT") (pinfunction "DO_2-DOUT") (pintype "output"))
      (node (ref "LED57") (pin "4-DIN") (pinfunction "DI_4-DIN") (pintype "input"))
    )
    (net (code "60") (name "Net-(LED57-DO)") (class "Default")
      (node (ref "LED57") (pin "2-DOUT") (pinfunction "DO_2-DOUT") (pintype "output"))
      (node (ref "LED58") (pin "4-DIN") (pinfunction "DI_4-DIN") (pintype "input"))
    )
    (net (code "61") (name "Net-(LED58-DO)") (class "Default")
      (node (ref "LED58") (pin "2-DOUT") (pinfunction "DO_2-DOUT") (pintype "output"))
      (node (ref "LED59") (pin "4-DIN") (pinfunction "DI_4-DIN") (pintype "input"))
    )
    (net (code "62") (name "Net-(LED59-DO)") (class "Default")
      (node (ref "LED59") (pin "2-DOUT") (pinfunction "DO_2-DOUT") (pintype "output"))
      (node (ref "LED60") (pin "4-DIN") (pinfunction "DI_4-DIN") (pintype "input"))
    )
    (net (code "63") (name "Net-(LED60-DO)") (class "Default")
      (node (ref "LED60") (pin "2-DOUT") (pinfunction "DO_2-DOUT") (pintype "output"))
      (node (ref "LED61") (pin "4-DIN") (pinfunction "DI_4-DIN") (pintype "input"))
    )
    (net (code "64") (name "VCC") (class "Default")
      (node (ref "C1") (pin "1") (pinfunction "1_1") (pintype "passive"))
      (node (ref "C10") (pin "1") (pinfunction "1_1") (pintype "passive"))
      (node (ref "C11") (pin "1") (pinfunction "1_1") (pintype "passive"))
      (node (ref "C12") (pin "1") (pinfunction "1_1") (pintype "passive"))
      (node (ref "C13") (pin "1") (pinfunction "1_1") (pintype "passive"))
      (node (ref "C14") (pin "1") (pinfunction "1_1") (pintype "passive"))
      (node (ref "C15") (pin "1") (pinfunction "1_1") (pintype "passive"))
      (node (ref "C16") (pin "1") (pinfunction "1_1") (pintype "passive"))
      (node (ref "C17") (pin "1") (pinfunction "1_1") (pintype "passive"))
      (node (ref "C18") (pin "1") (pinfunction "1_1") (pintype "passive"))
      (node (ref "C19") (pin "1") (pinfunction "1_1") (pintype "passive"))
      (node (ref "C2") (pin "1") (pinfunction "1_1") (pintype "passive"))
      (node (ref "C20") (pin "1") (pinfunction "1_1") (pintype "passive"))
      (node (ref "C21") (pin "1") (pinfunction "1_1") (pintype "passive"))
      (node (ref "C22") (pin "1") (pinfunction "1_1") (pintype "passive"))
      (node (ref "C23") (pin "1") (pinfunction "1_1") (pintype "passive"))
      (node (ref "C24") (pin "1") (pinfunction "1_1") (pintype "passive"))
      (node (ref "C25") (pin "1") (pinfunction "1_1") (pintype "passive"))
      (node (ref "C26") (pin "1") (pinfunction "1_1") (pintype "passive"))
      (node (ref "C27") (pin "1") (pinfunction "1_1") (pintype "passive"))
      (node (ref "C28") (pin "1") (pinfunction "1_1") (pintype "passive"))
      (node (ref "C29") (pin "1") (pinfunction "1_1") (pintype "passive"))
      (node (ref "C3") (pin "1") (pinfunction "1_1") (pintype "passive"))
      (node (ref "C30") (pin "1") (pinfunction "1_1") (pintype "passive"))
      (node (ref "C31") (pin "1") (pinfunction "1_1") (pintype "passive"))
      (node (ref "C32") (pin "1") (pinfunction "1_1") (pintype "passive"))
      (node (ref "C33") (pin "1") (pinfunction "1_1") (pintype "passive"))
      (node (ref "C34") (pin "1") (pinfunction "1_1") (pintype "passive"))
      (node (ref "C35") (pin "1") (pinfunction "1_1") (pintype "passive"))
      (node (ref "C36") (pin "1") (pinfunction "1_1") (pintype "passive"))
      (node (ref "C37") (pin "1") (pinfunction "1_1") (pintype "passive"))
      (node (ref "C38") (pin "1") (pinfunction "1_1") (pintype "passive"))
      (node (ref "C39") (pin "1") (pinfunction "1_1") (pintype "passive"))
      (node (ref "C4") (pin "1") (pinfunction "1_1") (pintype "passive"))
      (node (ref "C40") (pin "1") (pinfunction "1_1") (pintype "passive"))
      (node (ref "C41") (pin "1") (pinfunction "1_1") (pintype "passive"))
      (node (ref "C42") (pin "1") (pinfunction "1_1") (pintype "passive"))
      (node (ref "C43") (pin "1") (pinfunction "1_1") (pintype "passive"))
      (node (ref "C44") (pin "1") (pinfunction "1_1") (pintype "passive"))
      (node (ref "C45") (pin "1") (pinfunction "1_1") (pintype "passive"))
      (node (ref "C46") (pin "1") (pinfunction "1_1") (pintype "passive"))
      (node (ref "C47") (pin "1") (pinfunction "1_1") (pintype "passive"))
      (node (ref "C48") (pin "1") (pinfunction "1_1") (pintype "passive"))
      (node (ref "C49") (pin "1") (pinfunction "1_1") (pintype "passive"))
      (node (ref "C5") (pin "1") (pinfunction "1_1") (pintype "passive"))
      (node (ref "C50") (pin "1") (pinfunction "1_1") (pintype "passive"))
      (node (ref "C51") (pin "1") (pinfunction "1_1") (pintype "passive"))
      (node (ref "C52") (pin "1") (pinfunction "1_1") (pintype "passive"))
      (node (ref "C53") (pin "1") (pinfunction "1_1") (pintype "passive"))
      (node (ref "C54") (pin "1") (pinfunction "1_1") (pintype "passive"))
      (node (ref "C55") (pin "1") (pinfunction "1_1") (pintype "passive"))
      (node (ref "C56") (pin "1") (pinfunction "1_1") (pintype "passive"))
      (node (ref "C57") (pin "1") (pinfunction "1_1") (pintype "passive"))
      (node (ref "C58") (pin "1") (pinfunction "1_1") (pintype "passive"))
      (node (ref "C59") (pin "1") (pinfunction "1_1") (pintype "passive"))
      (node (ref "C6") (pin "1") (pinfunction "1_1") (pintype "passive"))
      (node (ref "C60") (pin "1") (pinfunction "1_1") (pintype "passive"))
      (node (ref "C61") (pin "1") (pinfunction "1_1") (pintype "passive"))
      (node (ref "C7") (pin "1") (pinfunction "1_1") (pintype "passive"))
      (node (ref "C8") (pin "1") (pinfunction "1_1") (pintype "passive"))
      (node (ref "C9") (pin "1") (pinfunction "1_1") (pintype "passive"))
      (node (ref "LED1") (pin "1-VDD") (pinfunction "VDD_1-VDD") (pintype "power_in"))
      (node (ref "LED10") (pin "1-VDD") (pinfunction "VDD_1-VDD") (pintype "power_in"))
      (node (ref "LED11") (pin "1-VDD") (pinfunction "VDD_1-VDD") (pintype "power_in"))
      (node (ref "LED12") (pin "1-VDD") (pinfunction "VDD_1-VDD") (pintype "power_in"))
      (node (ref "LED13") (pin "1-VDD") (pinfunction "VDD_1-VDD") (pintype "power_in"))
      (node (ref "LED14") (pin "1-VDD") (pinfunction "VDD_1-VDD") (pintype "power_in"))
      (node (ref "LED15") (pin "1-VDD") (pinfunction "VDD_1-VDD") (pintype "power_in"))
      (node (ref "LED16") (pin "1-VDD") (pinfunction "VDD_1-VDD") (pintype "power_in"))
      (node (ref "LED17") (pin "1-VDD") (pinfunction "VDD_1-VDD") (pintype "power_in"))
      (node (ref "LED18") (pin "1-VDD") (pinfunction "VDD_1-VDD") (pintype "power_in"))
      (node (ref "LED19") (pin "1-VDD") (pinfunction "VDD_1-VDD") (pintype "power_in"))
      (node (ref "LED2") (pin "1-VDD") (pinfunction "VDD_1-VDD") (pintype "power_in"))
      (node (ref "LED20") (pin "1-VDD") (pinfunction "VDD_1-VDD") (pintype "power_in"))
      (node (ref "LED21") (pin "1-VDD") (pinfunction "VDD_1-VDD") (pintype "power_in"))
      (node (ref "LED22") (pin "1-VDD") (pinfunction "VDD_1-VDD") (pintype "power_in"))
      (node (ref "LED23") (pin "1-VDD") (pinfunction "VDD_1-VDD") (pintype "power_in"))
      (node (ref "LED24") (pin "1-VDD") (pinfunction "VDD_1-VDD") (pintype "power_in"))
      (node (ref "LED25") (pin "1-VDD") (pinfunction "VDD_1-VDD") (pintype "power_in"))
      (node (ref "LED26") (pin "1-VDD") (pinfunction "VDD_1-VDD") (pintype "power_in"))
      (node (ref "LED27") (pin "1-VDD") (pinfunction "VDD_1-VDD") (pintype "power_in"))
      (node (ref "LED28") (pin "1-VDD") (pinfunction "VDD_1-VDD") (pintype "power_in"))
      (node (ref "LED29") (pin "1-VDD") (pinfunction "VDD_1-VDD") (pintype "power_in"))
      (node (ref "LED3") (pin "1-VDD") (pinfunction "VDD_1-VDD") (pintype "power_in"))
      (node (ref "LED30") (pin "1-VDD") (pinfunction "VDD_1-VDD") (pintype "power_in"))
      (node (ref "LED31") (pin "1-VDD") (pinfunction "VDD_1-VDD") (pintype "power_in"))
      (node (ref "LED32") (pin "1-VDD") (pinfunction "VDD_1-VDD") (pintype "power_in"))
      (node (ref "LED33") (pin "1-VDD") (pinfunction "VDD_1-VDD") (pintype "power_in"))
      (node (ref "LED34") (pin "1-VDD") (pinfunction "VDD_1-VDD") (pintype "power_in"))
      (node (ref "LED35") (pin "1-VDD") (pinfunction "VDD_1-VDD") (pintype "power_in"))
      (node (ref "LED36") (pin "1-VDD") (pinfunction "VDD_1-VDD") (pintype "power_in"))
      (node (ref "LED37") (pin "1-VDD") (pinfunction "VDD_1-VDD") (pintype "power_in"))
      (node (ref "LED38") (pin "1-VDD") (pinfunction "VDD_1-VDD") (pintype "power_in"))
      (node (ref "LED39") (pin "1-VDD") (pinfunction "VDD_1-VDD") (pintype "power_in"))
      (node (ref "LED4") (pin "1-VDD") (pinfunction "VDD_1-VDD") (pintype "power_in"))
      (node (ref "LED40") (pin "1-VDD") (pinfunction "VDD_1-VDD") (pintype "power_in"))
      (node (ref "LED41") (pin "1-VDD") (pinfunction "VDD_1-VDD") (pintype "power_in"))
      (node (ref "LED42") (pin "1-VDD") (pinfunction "VDD_1-VDD") (pintype "power_in"))
      (node (ref "LED43") (pin "1-VDD") (pinfunction "VDD_1-VDD") (pintype "power_in"))
      (node (ref "LED44") (pin "1-VDD") (pinfunction "VDD_1-VDD") (pintype "power_in"))
      (node (ref "LED45") (pin "1-VDD") (pinfunction "VDD_1-VDD") (pintype "power_in"))
      (node (ref "LED46") (pin "1-VDD") (pinfunction "VDD_1-VDD") (pintype "power_in"))
      (node (ref "LED47") (pin "1-VDD") (pinfunction "VDD_1-VDD") (pintype "power_in"))
      (node (ref "LED48") (pin "1-VDD") (pinfunction "VDD_1-VDD") (pintype "power_in"))
      (node (ref "LED49") (pin "1-VDD") (pinfunction "VDD_1-VDD") (pintype "power_in"))
      (node (ref "LED5") (pin "1-VDD") (pinfunction "VDD_1-VDD") (pintype "power_in"))
      (node (ref "LED50") (pin "1-VDD") (pinfunction "VDD_1-VDD") (pintype "power_in"))
      (node (ref "LED51") (pin "1-VDD") (pinfunction "VDD_1-VDD") (pintype "power_in"))
      (node (ref "LED52") (pin "1-VDD") (pinfunction "VDD_1-VDD") (pintype "power_in"))
      (node (ref "LED53") (pin "1-VDD") (pinfunction "VDD_1-VDD") (pintype "power_in"))
      (node (ref "LED54") (pin "1-VDD") (pinfunction "VDD_1-VDD") (pintype "power_in"))
      (node (ref "LED55") (pin "1-VDD") (pinfunction "VDD_1-VDD") (pintype "power_in"))
      (node (ref "LED56") (pin "1-VDD") (pinfunction "VDD_1-VDD") (pintype "power_in"))
      (node (ref "LED57") (pin "1-VDD") (pinfunction "VDD_1-VDD") (pintype "power_in"))
      (node (ref "LED58") (pin "1-VDD") (pinfunction "VDD_1-VDD") (pintype "power_in"))
      (node (ref "LED59") (pin "1-VDD") (pinfunction "VDD_1-VDD") (pintype "power_in"))
      (node (ref "LED6") (pin "1-VDD") (pinfunction "VDD_1-VDD") (pintype "power_in"))
      (node (ref "LED60") (pin "1-VDD") (pinfunction "VDD_1-VDD") (pintype "power_in"))
      (node (ref "LED61") (pin "1-VDD") (pinfunction "VDD_1-VDD") (pintype "power_in"))
      (node (ref "LED7") (pin "1-VDD") (pinfunction "VDD_1-VDD") (pintype "power_in"))
      (node (ref "LED8") (pin "1-VDD") (pinfunction "VDD_1-VDD") (pintype "power_in"))
      (node (ref "LED9") (pin "1-VDD") (pinfunction "VDD_1-VDD") (pintype "power_in"))
      (node (ref "X1") (pin "2") (pinfunction "S_2") (pintype "passive"))
    )
  )
)
